# final_esp32_pc_heart_v2_3.net
KiCad netlist of a schematic drawn in EAGLE
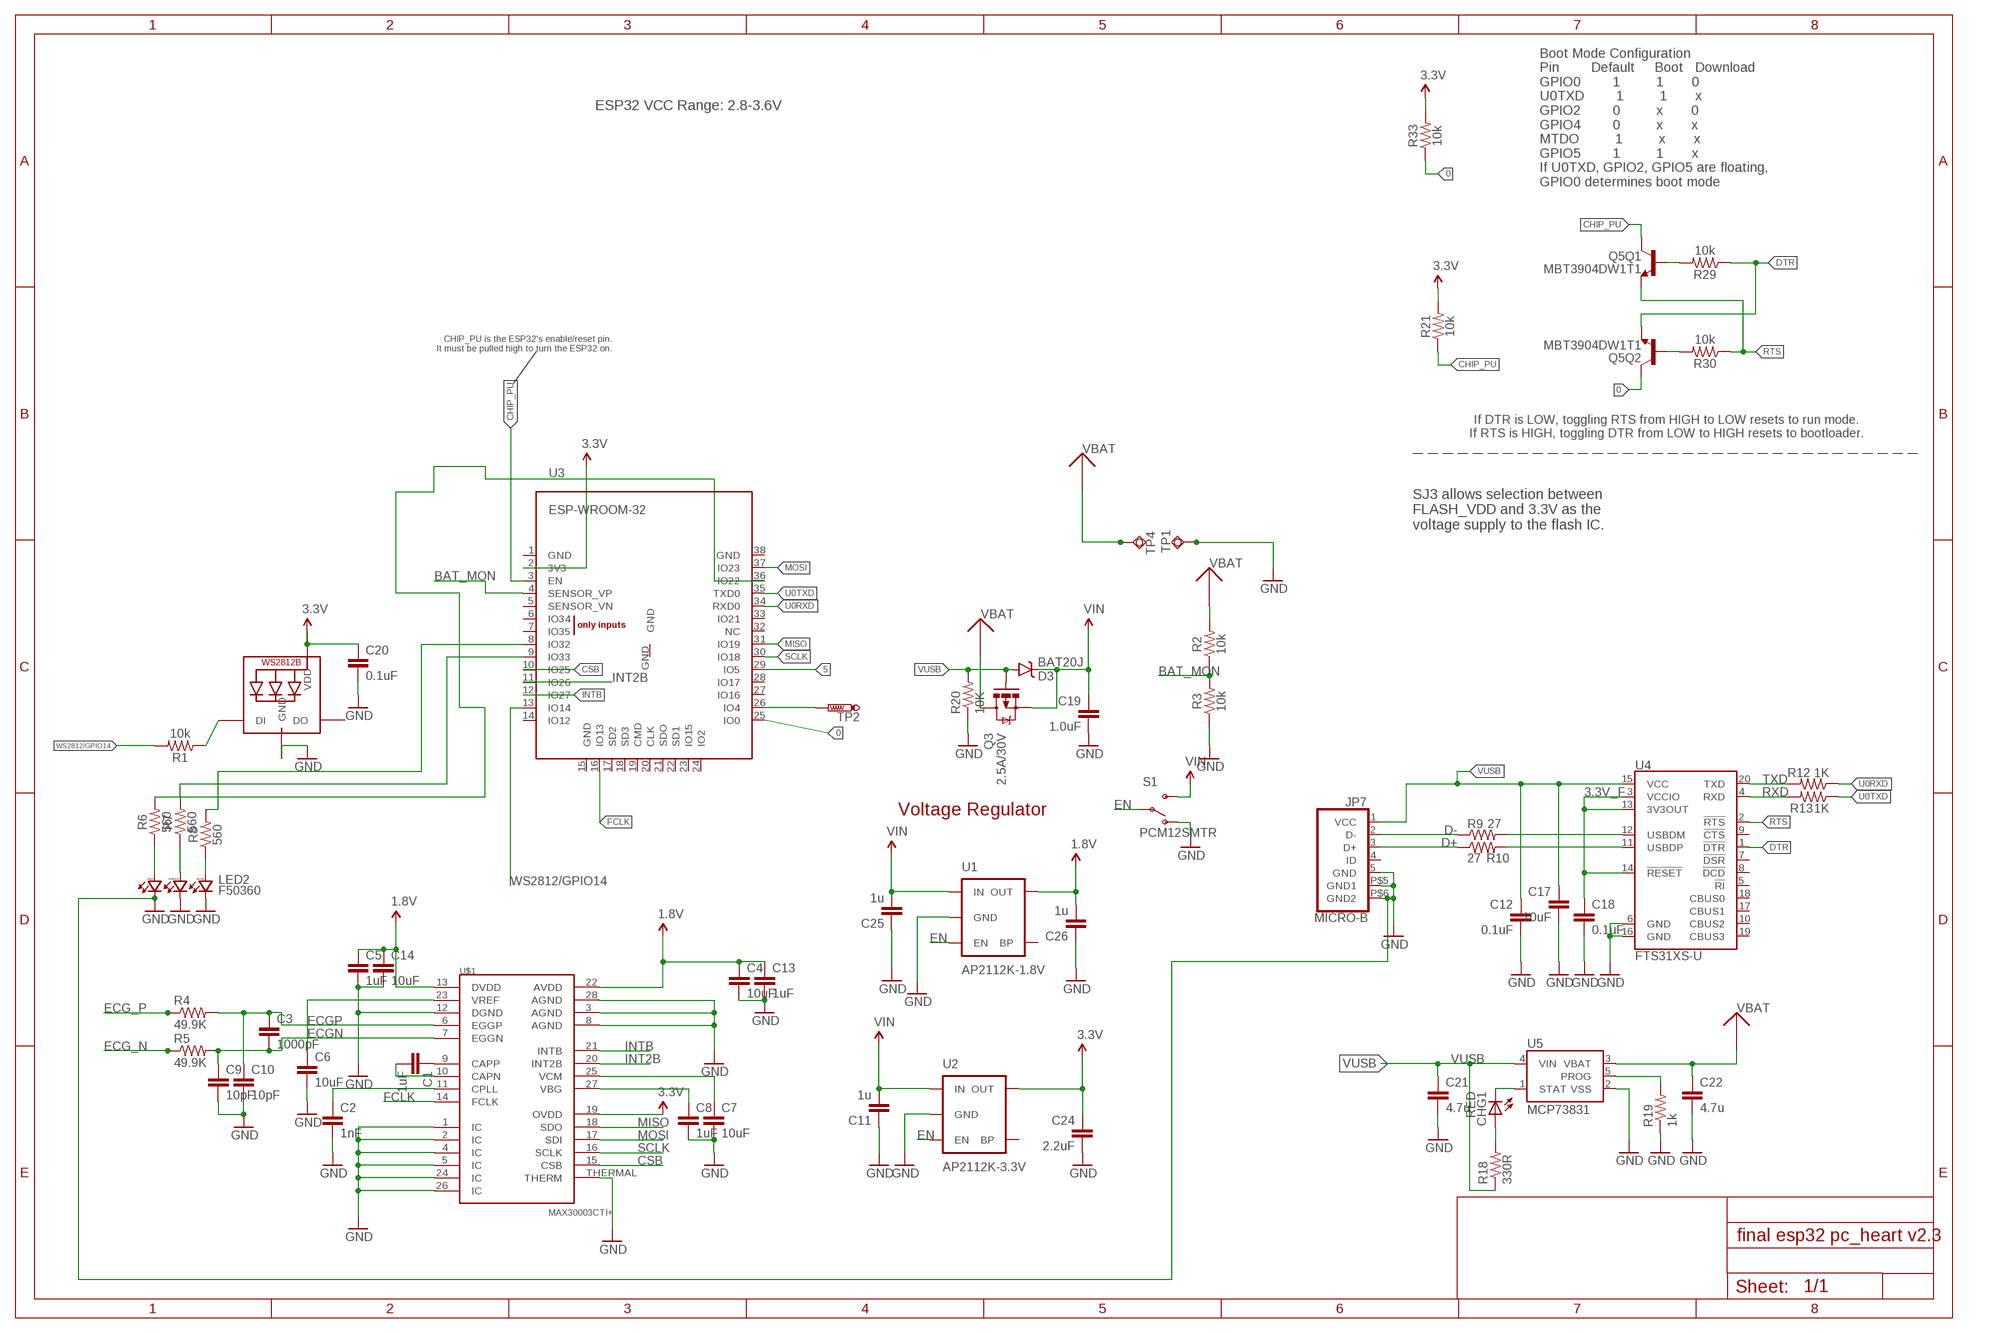
[diagram p0: schematic, sheet 1]

(export (version "E")
  (design (tool "Eeschema 10.0.6"))
  (components
    (comp (ref "C1")
      (value "1uF")
      (footprint "eagle-import:C0603")
      (libsource (lib "eagle-import") (part "C-EUC0603"))
    )
    (comp (ref "C2")
      (value "1nF")
      (footprint "eagle-import:C0603")
      (libsource (lib "eagle-import") (part "C-EUC0603"))
    )
    (comp (ref "C3")
      (value "1000pF")
      (footprint "eagle-import:C0402")
      (libsource (lib "eagle-import") (part "C-EUC0402"))
    )
    (comp (ref "C4")
      (value "10uF")
      (footprint "eagle-import:C0805")
      (libsource (lib "eagle-import") (part "C-EUC0805"))
    )
    (comp (ref "C5")
      (value "1uF")
      (footprint "eagle-import:C0402")
      (libsource (lib "eagle-import") (part "C-EUC0402"))
    )
    (comp (ref "C6")
      (value "10uF")
      (footprint "eagle-import:C0805")
      (libsource (lib "eagle-import") (part "C-EUC0805"))
    )
    (comp (ref "C7")
      (value "10uF")
      (footprint "eagle-import:C0805")
      (libsource (lib "eagle-import") (part "C-EUC0805"))
    )
    (comp (ref "C8")
      (value "1uF")
      (footprint "eagle-import:C0805")
      (libsource (lib "eagle-import") (part "C-EUC0805"))
    )
    (comp (ref "C9")
      (value "10pF")
      (footprint "eagle-import:C0402")
      (libsource (lib "eagle-import") (part "C-EUC0402"))
    )
    (comp (ref "C10")
      (value "10pF")
      (footprint "eagle-import:C0402")
      (libsource (lib "eagle-import") (part "C-EUC0402"))
    )
    (comp (ref "C11")
      (value "1u")
      (footprint "eagle-import:C0402")
      (libsource (lib "eagle-import") (part "C-EUC0402"))
    )
    (comp (ref "C12")
      (value "0.1uF")
      (footprint "eagle-import:C0402")
      (libsource (lib "eagle-import") (part "C-EUC0402"))
    )
    (comp (ref "C13")
      (value "1uF")
      (footprint "eagle-import:C0805")
      (libsource (lib "eagle-import") (part "C-EUC0805"))
    )
    (comp (ref "C14")
      (value "10uF")
      (footprint "eagle-import:C0603")
      (libsource (lib "eagle-import") (part "C-EUC0603"))
    )
    (comp (ref "C17")
      (value "10uF")
      (footprint "eagle-import:C0805")
      (libsource (lib "eagle-import") (part "C-EUC0805"))
    )
    (comp (ref "C18")
      (value "0.1uF")
      (footprint "eagle-import:C0402")
      (libsource (lib "eagle-import") (part "C-EUC0402"))
    )
    (comp (ref "C19")
      (value "1.0uF")
      (footprint "eagle-import:C0402")
      (libsource (lib "eagle-import") (part "C-EUC0402"))
    )
    (comp (ref "C20")
      (value "0.1uF")
      (footprint "eagle-import:0603")
      (libsource (lib "eagle-import") (part "0.1UF-0603-25V-(+80/-20%)"))
    )
    (comp (ref "C21")
      (value "4.7u")
      (footprint "eagle-import:C0805")
      (libsource (lib "eagle-import") (part "C-EUC0805"))
    )
    (comp (ref "C22")
      (value "4.7u")
      (footprint "eagle-import:C0805")
      (libsource (lib "eagle-import") (part "C-EUC0805"))
    )
    (comp (ref "C24")
      (value "2.2uF")
      (footprint "eagle-import:C0603")
      (libsource (lib "eagle-import") (part "C-EUC0603"))
    )
    (comp (ref "C25")
      (value "1u")
      (footprint "eagle-import:C0402")
      (libsource (lib "eagle-import") (part "C-EUC0402"))
    )
    (comp (ref "C26")
      (value "1u")
      (footprint "eagle-import:C0402")
      (libsource (lib "eagle-import") (part "C-EUC0402"))
    )
    (comp (ref "CHG1")
      (value "RED")
      (footprint "eagle-import:CHIPLED_0603")
      (libsource (lib "eagle-import") (part "LEDCHIPLED_0603"))
    )
    (comp (ref "D3")
      (value "BAT20J")
      (footprint "eagle-import:SOD-323")
      (libsource (lib "eagle-import") (part "DIODE-SCHOTTKY-BAT20J"))
    )
    (comp (ref "JP7")
      (value "MICRO-B")
      (footprint "eagle-import:MICRO-B")
      (libsource (lib "eagle-import") (part "MICRO-B"))
    )
    (comp (ref "LED1")
      (value "WS2812B5050")
      (footprint "eagle-import:WS2812B")
      (libsource (lib "eagle-import") (part "WS2812B5050"))
    )
    (comp (ref "LED2")
      (value "F50360")
      (footprint "eagle-import:F50360")
      (libsource (lib "eagle-import") (part "F50360"))
    )
    (comp (ref "Q3")
      (value "2.5A/30V")
      (footprint "eagle-import:SOT23-3")
      (libsource (lib "eagle-import") (part "MOSFET-PCHANNELDMG2307L"))
    )
    (comp (ref "Q5")
      (value "MBT3904DW1T1")
      (footprint "eagle-import:SC70-6")
      (libsource (lib "eagle-import") (part "MBT3904DW1T1"))
    )
    (comp (ref "R1")
      (value "10k")
      (footprint "eagle-import:0603")
      (libsource (lib "eagle-import") (part "10KOHM-1/10W-1%(0603)0603"))
    )
    (comp (ref "R2")
      (value "10k")
      (footprint "eagle-import:0603")
      (libsource (lib "eagle-import") (part "10KOHM-1/10W-1%(0603)0603"))
    )
    (comp (ref "R3")
      (value "10k")
      (footprint "eagle-import:0603")
      (libsource (lib "eagle-import") (part "10KOHM-1/10W-1%(0603)0603"))
    )
    (comp (ref "R4")
      (value "49.9K")
      (footprint "eagle-import:0805")
      (libsource (lib "eagle-import") (part "RESISTOR0805-RES"))
    )
    (comp (ref "R5")
      (value "49.9K")
      (footprint "eagle-import:0805")
      (libsource (lib "eagle-import") (part "RESISTOR0805-RES"))
    )
    (comp (ref "R6")
      (value "560")
      (footprint "eagle-import:0603")
      (libsource (lib "eagle-import") (part "10KOHM-1/10W-1%(0603)0603"))
    )
    (comp (ref "R7")
      (value "560")
      (footprint "eagle-import:0603")
      (libsource (lib "eagle-import") (part "10KOHM-1/10W-1%(0603)0603"))
    )
    (comp (ref "R8")
      (value "560")
      (footprint "eagle-import:0603")
      (libsource (lib "eagle-import") (part "10KOHM-1/10W-1%(0603)0603"))
    )
    (comp (ref "R9")
      (value "27")
      (footprint "eagle-import:R0402")
      (libsource (lib "eagle-import") (part "R-US_R0402"))
    )
    (comp (ref "R10")
      (value "27")
      (footprint "eagle-import:R0402")
      (libsource (lib "eagle-import") (part "R-US_R0402"))
    )
    (comp (ref "R12")
      (value "1K")
      (footprint "eagle-import:R0402")
      (libsource (lib "eagle-import") (part "R-US_R0402"))
    )
    (comp (ref "R13")
      (value "1K")
      (footprint "eagle-import:R0402")
      (libsource (lib "eagle-import") (part "R-US_R0402"))
    )
    (comp (ref "R18")
      (value "330R")
      (footprint "eagle-import:R0402")
      (libsource (lib "eagle-import") (part "R-US_R0402"))
    )
    (comp (ref "R19")
      (value "1k")
      (footprint "eagle-import:R0402")
      (libsource (lib "eagle-import") (part "R-US_R0402"))
    )
    (comp (ref "R20")
      (value "10K")
      (footprint "eagle-import:R0402")
      (libsource (lib "eagle-import") (part "R-US_R0402"))
    )
    (comp (ref "R21")
      (value "10k")
      (footprint "eagle-import:0603")
      (libsource (lib "eagle-import") (part "10KOHM-1/10W-1%(0603)0603"))
    )
    (comp (ref "R29")
      (value "10k")
      (footprint "eagle-import:0603")
      (libsource (lib "eagle-import") (part "10KOHM-0603-1/10W-1%"))
    )
    (comp (ref "R30")
      (value "10k")
      (footprint "eagle-import:0603")
      (libsource (lib "eagle-import") (part "10KOHM-0603-1/10W-1%"))
    )
    (comp (ref "R33")
      (value "10k")
      (footprint "eagle-import:0603")
      (libsource (lib "eagle-import") (part "10KOHM-1/10W-1%(0603)0603"))
    )
    (comp (ref "S1")
      (value "PCM12SMTR")
      (footprint "eagle-import:SWITCH-SPST-SMD-A")
      (libsource (lib "eagle-import") (part "SWITCH-SPDT-SMD-A"))
    )
    (comp (ref "TP1")
      (value "TPSQTP20SQ")
      (footprint "eagle-import:TP20SQ")
      (libsource (lib "eagle-import") (part "TPSQTP20SQ"))
    )
    (comp (ref "TP2")
      (value "PTR1TP10SQ")
      (footprint "eagle-import:TP10SQ")
      (libsource (lib "eagle-import") (part "PTR1TP10SQ"))
    )
    (comp (ref "TP4")
      (value "TPSQTP20SQ")
      (footprint "eagle-import:TP20SQ")
      (libsource (lib "eagle-import") (part "TPSQTP20SQ"))
    )
    (comp (ref "U$1")
      (value "MAX30003CTI+")
      (footprint "eagle-import:QFN-28")
      (libsource (lib "eagle-import") (part "MAX30003"))
    )
    (comp (ref "U1")
      (value "AP2112K-1.8V")
      (footprint "eagle-import:SOT23-5")
      (libsource (lib "eagle-import") (part "V_REG_LDOSMD"))
    )
    (comp (ref "U2")
      (value "AP2112K-3.3V")
      (footprint "eagle-import:SOT23-5")
      (libsource (lib "eagle-import") (part "V_REG_LDOSMD"))
    )
    (comp (ref "U3")
      (value "ESP-WROOM-32")
      (footprint "eagle-import:ESP-WROOM-32")
      (libsource (lib "eagle-import") (part "ESP-WROOM-32"))
    )
    (comp (ref "U4")
      (value "FTS31XS-U")
      (footprint "eagle-import:SSOP20_L")
      (libsource (lib "eagle-import") (part "FT231XS"))
    )
    (comp (ref "U5")
      (value "MCP73831")
      (footprint "eagle-import:SOT23-5")
      (libsource (lib "eagle-import") (part "MCP73831"))
    )
  )
  (nets
    (net (code "1") (name "/3.3V_F") (class "Default")
      (node (ref "C18") (pin "1") (pinfunction "1_1") (pintype "passive"))
      (node (ref "U4") (pin "13") (pinfunction "3V3OUT_13") (pintype "bidirectional"))
      (node (ref "U4") (pin "14") (pinfunction "~{RESET}_14") (pintype "bidirectional"))
      (node (ref "U4") (pin "3") (pinfunction "VCCIO_3") (pintype "bidirectional"))
    )
    (net (code "2") (name "/BAT_MON") (class "Default")
      (node (ref "R2") (pin "1") (pinfunction "1_1") (pintype "passive"))
      (node (ref "R3") (pin "2") (pinfunction "2_2") (pintype "passive"))
      (node (ref "U3") (pin "4") (pinfunction "SENSOR_VP_4") (pintype "input"))
    )
    (net (code "3") (name "/D+") (class "Default")
      (node (ref "JP7") (pin "3") (pinfunction "D+_3") (pintype "bidirectional"))
      (node (ref "R10") (pin "1") (pinfunction "1_1") (pintype "passive"))
    )
    (net (code "4") (name "/D-") (class "Default")
      (node (ref "JP7") (pin "2") (pinfunction "D-_2") (pintype "bidirectional"))
      (node (ref "R9") (pin "1") (pinfunction "1_1") (pintype "passive"))
    )
    (net (code "5") (name "/ECGN") (class "Default")
      (node (ref "C3") (pin "2") (pinfunction "2_2") (pintype "passive"))
      (node (ref "C9") (pin "1") (pinfunction "1_1") (pintype "passive"))
      (node (ref "R5") (pin "2") (pinfunction "2_2") (pintype "passive"))
      (node (ref "U$1") (pin "7") (pinfunction "EGGN_7") (pintype "bidirectional"))
    )
    (net (code "6") (name "/ECGP") (class "Default")
      (node (ref "C10") (pin "1") (pinfunction "1_1") (pintype "passive"))
      (node (ref "C3") (pin "1") (pinfunction "1_1") (pintype "passive"))
      (node (ref "R4") (pin "2") (pinfunction "2_2") (pintype "passive"))
      (node (ref "U$1") (pin "6") (pinfunction "EGGP_6") (pintype "bidirectional"))
    )
    (net (code "7") (name "/ECG_N") (class "Default")
      (node (ref "R5") (pin "1") (pinfunction "1_1") (pintype "passive"))
    )
    (net (code "8") (name "/ECG_P") (class "Default")
      (node (ref "R4") (pin "1") (pinfunction "1_1") (pintype "passive"))
    )
    (net (code "9") (name "/EN") (class "Default")
      (node (ref "S1") (pin "2") (pinfunction "P_2") (pintype "passive"))
      (node (ref "U1") (pin "3") (pinfunction "EN_3") (pintype "input"))
      (node (ref "U2") (pin "3") (pinfunction "EN_3") (pintype "input"))
    )
    (net (code "10") (name "/INT2B") (class "Default")
      (node (ref "U$1") (pin "20") (pinfunction "INT2B_20") (pintype "bidirectional"))
      (node (ref "U3") (pin "11") (pinfunction "IO26_11") (pintype "bidirectional"))
    )
    (net (code "11") (name "/RXD") (class "Default")
      (node (ref "R13") (pin "2") (pinfunction "2_2") (pintype "passive"))
      (node (ref "U4") (pin "4") (pinfunction "RXD_4") (pintype "bidirectional"))
    )
    (net (code "12") (name "/TXD") (class "Default")
      (node (ref "R12") (pin "2") (pinfunction "2_2") (pintype "passive"))
      (node (ref "U4") (pin "20") (pinfunction "TXD_20") (pintype "bidirectional"))
    )
    (net (code "13") (name "0") (class "Default")
      (node (ref "Q5") (pin "6") (pinfunction "C_6") (pintype "passive"))
      (node (ref "R33") (pin "1") (pinfunction "1_1") (pintype "passive"))
      (node (ref "U3") (pin "25") (pinfunction "IO0_25") (pintype "bidirectional"))
    )
    (net (code "14") (name "1.8V") (class "Default")
      (node (ref "C13") (pin "1") (pinfunction "1_1") (pintype "passive"))
      (node (ref "C14") (pin "1") (pinfunction "1_1") (pintype "passive"))
      (node (ref "C26") (pin "2") (pinfunction "2_2") (pintype "passive"))
      (node (ref "C4") (pin "1") (pinfunction "1_1") (pintype "passive"))
      (node (ref "C5") (pin "1") (pinfunction "1_1") (pintype "passive"))
      (node (ref "U$1") (pin "13") (pinfunction "DVDD_13") (pintype "bidirectional"))
      (node (ref "U$1") (pin "22") (pinfunction "AVDD_22") (pintype "bidirectional"))
      (node (ref "U1") (pin "5") (pinfunction "OUT_5") (pintype "passive"))
    )
    (net (code "15") (name "3.3V") (class "Default")
      (node (ref "C20") (pin "1") (pinfunction "1_1") (pintype "passive"))
      (node (ref "C24") (pin "1") (pinfunction "1_1") (pintype "passive"))
      (node (ref "LED1") (pin "1-VDD") (pinfunction "VDD_1-VDD") (pintype "power_in"))
      (node (ref "R21") (pin "2") (pinfunction "2_2") (pintype "passive"))
      (node (ref "R33") (pin "2") (pinfunction "2_2") (pintype "passive"))
      (node (ref "U$1") (pin "19") (pinfunction "OVDD_19") (pintype "bidirectional"))
      (node (ref "U2") (pin "5") (pinfunction "OUT_5") (pintype "passive"))
      (node (ref "U3") (pin "2") (pinfunction "3V3_2") (pintype "bidirectional"))
    )
    (net (code "16") (name "5") (class "Default")
      (node (ref "U3") (pin "29") (pinfunction "IO5_29") (pintype "bidirectional"))
    )
    (net (code "17") (name "CHIP_PU") (class "Default")
      (node (ref "Q5") (pin "3") (pinfunction "C_3") (pintype "passive"))
      (node (ref "R21") (pin "1") (pinfunction "1_1") (pintype "passive"))
      (node (ref "U3") (pin "3") (pinfunction "EN_3") (pintype "bidirectional"))
    )
    (net (code "18") (name "CSB") (class "Default")
      (node (ref "U$1") (pin "15") (pinfunction "CSB_15") (pintype "bidirectional"))
      (node (ref "U3") (pin "10") (pinfunction "IO25_10") (pintype "bidirectional"))
    )
    (net (code "19") (name "DTR") (class "Default")
      (node (ref "Q5") (pin "1") (pinfunction "E_1") (pintype "passive"))
      (node (ref "R29") (pin "1") (pinfunction "1_1") (pintype "passive"))
      (node (ref "U4") (pin "1") (pinfunction "~{DTR}_1") (pintype "bidirectional"))
    )
    (net (code "20") (name "FCLK") (class "Default")
      (node (ref "U$1") (pin "14") (pinfunction "FCLK_14") (pintype "bidirectional"))
      (node (ref "U3") (pin "16") (pinfunction "IO13_16") (pintype "bidirectional"))
    )
    (net (code "21") (name "GND") (class "Default")
      (node (ref "C10") (pin "2") (pinfunction "2_2") (pintype "passive"))
      (node (ref "C11") (pin "1") (pinfunction "1_1") (pintype "passive"))
      (node (ref "C12") (pin "2") (pinfunction "2_2") (pintype "passive"))
      (node (ref "C13") (pin "2") (pinfunction "2_2") (pintype "passive"))
      (node (ref "C14") (pin "2") (pinfunction "2_2") (pintype "passive"))
      (node (ref "C17") (pin "2") (pinfunction "2_2") (pintype "passive"))
      (node (ref "C18") (pin "2") (pinfunction "2_2") (pintype "passive"))
      (node (ref "C19") (pin "2") (pinfunction "2_2") (pintype "passive"))
      (node (ref "C2") (pin "2") (pinfunction "2_2") (pintype "passive"))
      (node (ref "C20") (pin "2") (pinfunction "2_2") (pintype "passive"))
      (node (ref "C21") (pin "2") (pinfunction "2_2") (pintype "passive"))
      (node (ref "C22") (pin "2") (pinfunction "2_2") (pintype "passive"))
      (node (ref "C24") (pin "2") (pinfunction "2_2") (pintype "passive"))
      (node (ref "C25") (pin "1") (pinfunction "1_1") (pintype "passive"))
      (node (ref "C26") (pin "1") (pinfunction "1_1") (pintype "passive"))
      (node (ref "C4") (pin "2") (pinfunction "2_2") (pintype "passive"))
      (node (ref "C5") (pin "2") (pinfunction "2_2") (pintype "passive"))
      (node (ref "C6") (pin "2") (pinfunction "2_2") (pintype "passive"))
      (node (ref "C7") (pin "2") (pinfunction "2_2") (pintype "passive"))
      (node (ref "C8") (pin "2") (pinfunction "2_2") (pintype "passive"))
      (node (ref "C9") (pin "2") (pinfunction "2_2") (pintype "passive"))
      (node (ref "JP7") (pin "5") (pinfunction "GND_5") (pintype "bidirectional"))
      (node (ref "JP7") (pin "P$5") (pinfunction "GND1_P$5") (pintype "bidirectional"))
      (node (ref "JP7") (pin "P$6") (pinfunction "GND2_P$6") (pintype "bidirectional"))
      (node (ref "LED1") (pin "3-GND") (pinfunction "GND_3-GND") (pintype "power_in"))
      (node (ref "LED2") (pin "BC") (pinfunction "BC_BC") (pintype "passive"))
      (node (ref "LED2") (pin "GC") (pinfunction "GC_GC") (pintype "passive"))
      (node (ref "LED2") (pin "RC") (pinfunction "RC_RC") (pintype "passive"))
      (node (ref "R19") (pin "1") (pinfunction "1_1") (pintype "passive"))
      (node (ref "R20") (pin "1") (pinfunction "1_1") (pintype "passive"))
      (node (ref "R3") (pin "1") (pinfunction "1_1") (pintype "passive"))
      (node (ref "S1") (pin "1") (pinfunction "O_1") (pintype "passive"))
      (node (ref "TP1") (pin "TP") (pinfunction "TP_TP") (pintype "input"))
      (node (ref "U$1") (pin "1") (pinfunction "IC_1") (pintype "bidirectional"))
      (node (ref "U$1") (pin "12") (pinfunction "DGND_12") (pintype "bidirectional"))
      (node (ref "U$1") (pin "2") (pinfunction "IC_2") (pintype "bidirectional"))
      (node (ref "U$1") (pin "24") (pinfunction "IC_24") (pintype "bidirectional"))
      (node (ref "U$1") (pin "26") (pinfunction "IC_26") (pintype "bidirectional"))
      (node (ref "U$1") (pin "28") (pinfunction "AGND_28") (pintype "bidirectional"))
      (node (ref "U$1") (pin "3") (pinfunction "AGND_3") (pintype "bidirectional"))
      (node (ref "U$1") (pin "4") (pinfunction "IC_4") (pintype "bidirectional"))
      (node (ref "U$1") (pin "5") (pinfunction "IC_5") (pintype "bidirectional"))
      (node (ref "U$1") (pin "8") (pinfunction "AGND_8") (pintype "bidirectional"))
      (node (ref "U$1") (pin "THERMAL") (pinfunction "THERM_THERMAL") (pintype "bidirectional"))
      (node (ref "U1") (pin "2") (pinfunction "GND_2") (pintype "input"))
      (node (ref "U2") (pin "2") (pinfunction "GND_2") (pintype "input"))
      (node (ref "U4") (pin "16") (pinfunction "GND_16") (pintype "bidirectional"))
      (node (ref "U4") (pin "6") (pinfunction "GND_6") (pintype "bidirectional"))
      (node (ref "U5") (pin "2") (pinfunction "VSS_2") (pintype "power_in"))
    )
    (net (code "22") (name "INTB") (class "Default")
      (node (ref "U$1") (pin "21") (pinfunction "INTB_21") (pintype "bidirectional"))
      (node (ref "U3") (pin "12") (pinfunction "IO27_12") (pintype "bidirectional"))
    )
    (net (code "23") (name "MISO") (class "Default")
      (node (ref "U$1") (pin "18") (pinfunction "SDO_18") (pintype "bidirectional"))
      (node (ref "U3") (pin "31") (pinfunction "IO19_31") (pintype "bidirectional"))
    )
    (net (code "24") (name "MOSI") (class "Default")
      (node (ref "U$1") (pin "17") (pinfunction "SDI_17") (pintype "bidirectional"))
      (node (ref "U3") (pin "37") (pinfunction "IO23_37") (pintype "bidirectional"))
    )
    (net (code "25") (name "Net-(CHG1-PadA)") (class "Default")
      (node (ref "CHG1") (pin "A") (pinfunction "A_A") (pintype "passive"))
      (node (ref "R18") (pin "2") (pinfunction "2_2") (pintype "passive"))
    )
    (net (code "26") (name "Net-(LED1-DI)") (class "Default")
      (node (ref "LED1") (pin "4-DIN") (pinfunction "DI_4-DIN") (pintype "input"))
      (node (ref "R1") (pin "1") (pinfunction "1_1") (pintype "passive"))
    )
    (net (code "27") (name "Net-(LED2-PadBA)") (class "Default")
      (node (ref "LED2") (pin "BA") (pinfunction "BA_BA") (pintype "passive"))
      (node (ref "R8") (pin "1") (pinfunction "1_1") (pintype "passive"))
    )
    (net (code "28") (name "Net-(LED2-PadGA)") (class "Default")
      (node (ref "LED2") (pin "GA") (pinfunction "GA_GA") (pintype "passive"))
      (node (ref "R7") (pin "1") (pinfunction "1_1") (pintype "passive"))
    )
    (net (code "29") (name "Net-(LED2-PadRA)") (class "Default")
      (node (ref "LED2") (pin "RA") (pinfunction "RA_RA") (pintype "passive"))
      (node (ref "R6") (pin "1") (pinfunction "1_1") (pintype "passive"))
    )
    (net (code "30") (name "Net-(Q5A-B)") (class "Default")
      (node (ref "Q5") (pin "5") (pinfunction "B_5") (pintype "passive"))
      (node (ref "R29") (pin "2") (pinfunction "2_2") (pintype "passive"))
    )
    (net (code "31") (name "Net-(Q5B-B)") (class "Default")
      (node (ref "Q5") (pin "2") (pinfunction "B_2") (pintype "passive"))
      (node (ref "R30") (pin "2") (pinfunction "2_2") (pintype "passive"))
    )
    (net (code "32") (name "Net-(U$1-CAPN)") (class "Default")
      (node (ref "C1") (pin "2") (pinfunction "2_2") (pintype "passive"))
      (node (ref "U$1") (pin "10") (pinfunction "CAPN_10") (pintype "bidirectional"))
    )
    (net (code "33") (name "Net-(U$1-CAPP)") (class "Default")
      (node (ref "C1") (pin "1") (pinfunction "1_1") (pintype "passive"))
      (node (ref "U$1") (pin "9") (pinfunction "CAPP_9") (pintype "bidirectional"))
    )
    (net (code "34") (name "Net-(U$1-CPLL)") (class "Default")
      (node (ref "C2") (pin "1") (pinfunction "1_1") (pintype "passive"))
      (node (ref "U$1") (pin "11") (pinfunction "CPLL_11") (pintype "bidirectional"))
    )
    (net (code "35") (name "Net-(U$1-VBG)") (class "Default")
      (node (ref "C8") (pin "1") (pinfunction "1_1") (pintype "passive"))
      (node (ref "U$1") (pin "27") (pinfunction "VBG_27") (pintype "bidirectional"))
    )
    (net (code "36") (name "Net-(U$1-VCM)") (class "Default")
      (node (ref "C7") (pin "1") (pinfunction "1_1") (pintype "passive"))
      (node (ref "U$1") (pin "25") (pinfunction "VCM_25") (pintype "bidirectional"))
    )
    (net (code "37") (name "Net-(U$1-VREF)") (class "Default")
      (node (ref "C6") (pin "1") (pinfunction "1_1") (pintype "passive"))
      (node (ref "U$1") (pin "23") (pinfunction "VREF_23") (pintype "bidirectional"))
    )
    (net (code "38") (name "Net-(U3-IO4)") (class "Default")
      (node (ref "TP2") (pin "TP") (pinfunction "TP_TP") (pintype "input"))
      (node (ref "U3") (pin "26") (pinfunction "IO4_26") (pintype "bidirectional"))
    )
    (net (code "39") (name "Net-(U3-IO22)") (class "Default")
      (node (ref "R6") (pin "2") (pinfunction "2_2") (pintype "passive"))
      (node (ref "U3") (pin "36") (pinfunction "IO22_36") (pintype "bidirectional"))
    )
    (net (code "40") (name "Net-(U3-IO32)") (class "Default")
      (node (ref "R8") (pin "2") (pinfunction "2_2") (pintype "passive"))
      (node (ref "U3") (pin "8") (pinfunction "IO32_8") (pintype "bidirectional"))
    )
    (net (code "41") (name "Net-(U3-IO33)") (class "Default")
      (node (ref "R7") (pin "2") (pinfunction "2_2") (pintype "passive"))
      (node (ref "U3") (pin "9") (pinfunction "IO33_9") (pintype "bidirectional"))
    )
    (net (code "42") (name "Net-(U4-USBDM)") (class "Default")
      (node (ref "R9") (pin "2") (pinfunction "2_2") (pintype "passive"))
      (node (ref "U4") (pin "12") (pinfunction "USBDM_12") (pintype "bidirectional"))
    )
    (net (code "43") (name "Net-(U4-USBDP)") (class "Default")
      (node (ref "R10") (pin "2") (pinfunction "2_2") (pintype "passive"))
      (node (ref "U4") (pin "11") (pinfunction "USBDP_11") (pintype "bidirectional"))
    )
    (net (code "44") (name "Net-(U5-PROG)") (class "Default")
      (node (ref "R19") (pin "2") (pinfunction "2_2") (pintype "passive"))
      (node (ref "U5") (pin "5") (pinfunction "PROG_5") (pintype "input"))
    )
    (net (code "45") (name "Net-(U5-STAT)") (class "Default")
      (node (ref "CHG1") (pin "C") (pinfunction "C_C") (pintype "passive"))
      (node (ref "U5") (pin "1") (pinfunction "STAT_1") (pintype "output"))
    )
    (net (code "46") (name "RTS") (class "Default")
      (node (ref "Q5") (pin "4") (pinfunction "E_4") (pintype "passive"))
      (node (ref "R30") (pin "1") (pinfunction "1_1") (pintype "passive"))
      (node (ref "U4") (pin "2") (pinfunction "~{RTS}_2") (pintype "bidirectional"))
    )
    (net (code "47") (name "SCLK") (class "Default")
      (node (ref "U$1") (pin "16") (pinfunction "SCLK_16") (pintype "bidirectional"))
      (node (ref "U3") (pin "30") (pinfunction "IO18_30") (pintype "bidirectional"))
    )
    (net (code "48") (name "U0RXD") (class "Default")
      (node (ref "R12") (pin "1") (pinfunction "1_1") (pintype "passive"))
      (node (ref "U3") (pin "34") (pinfunction "RXD0_34") (pintype "bidirectional"))
    )
    (net (code "49") (name "U0TXD") (class "Default")
      (node (ref "R13") (pin "1") (pinfunction "1_1") (pintype "passive"))
      (node (ref "U3") (pin "35") (pinfunction "TXD0_35") (pintype "bidirectional"))
    )
    (net (code "50") (name "VBAT") (class "Default")
      (node (ref "C22") (pin "1") (pinfunction "1_1") (pintype "passive"))
      (node (ref "Q3") (pin "3") (pinfunction "D_3") (pintype "passive"))
      (node (ref "R2") (pin "2") (pinfunction "2_2") (pintype "passive"))
      (node (ref "TP4") (pin "TP") (pinfunction "TP_TP") (pintype "input"))
      (node (ref "U5") (pin "3") (pinfunction "VBAT_3") (pintype "power_in"))
    )
    (net (code "51") (name "VIN") (class "Default")
      (node (ref "C11") (pin "2") (pinfunction "2_2") (pintype "passive"))
      (node (ref "C19") (pin "1") (pinfunction "1_1") (pintype "passive"))
      (node (ref "C25") (pin "2") (pinfunction "2_2") (pintype "passive"))
      (node (ref "D3") (pin "C") (pinfunction "C_C") (pintype "passive"))
      (node (ref "Q3") (pin "2") (pinfunction "S_2") (pintype "passive"))
      (node (ref "S1") (pin "3") (pinfunction "S_3") (pintype "passive"))
      (node (ref "U1") (pin "1") (pinfunction "IN_1") (pintype "input"))
      (node (ref "U2") (pin "1") (pinfunction "IN_1") (pintype "input"))
    )
    (net (code "52") (name "VUSB") (class "Default")
      (node (ref "C12") (pin "1") (pinfunction "1_1") (pintype "passive"))
      (node (ref "C17") (pin "1") (pinfunction "1_1") (pintype "passive"))
      (node (ref "C21") (pin "1") (pinfunction "1_1") (pintype "passive"))
      (node (ref "D3") (pin "A") (pinfunction "A_A") (pintype "passive"))
      (node (ref "JP7") (pin "1") (pinfunction "VCC_1") (pintype "bidirectional"))
      (node (ref "Q3") (pin "1") (pinfunction "G_1") (pintype "passive"))
      (node (ref "R18") (pin "1") (pinfunction "1_1") (pintype "passive"))
      (node (ref "R20") (pin "2") (pinfunction "2_2") (pintype "passive"))
      (node (ref "U4") (pin "15") (pinfunction "VCC_15") (pintype "bidirectional"))
      (node (ref "U5") (pin "4") (pinfunction "VIN_4") (pintype "power_in"))
    )
    (net (code "53") (name "WS2812{slash}GPIO14") (class "Default")
      (node (ref "R1") (pin "2") (pinfunction "2_2") (pintype "passive"))
      (node (ref "U3") (pin "13") (pinfunction "IO14_13") (pintype "bidirectional"))
    )
    (net (code "54") (name "unconnected-(JP7-ID-Pad4)") (class "Default")
      (node (ref "JP7") (pin "4") (pinfunction "ID_4") (pintype "bidirectional"))
    )
    (net (code "55") (name "unconnected-(LED1-DO-Pad2-DOUT)") (class "Default")
      (node (ref "LED1") (pin "2-DOUT") (pinfunction "DO_2-DOUT") (pintype "output"))
    )
    (net (code "56") (name "unconnected-(U1-BP-Pad4)") (class "Default")
      (node (ref "U1") (pin "4") (pinfunction "BP_4") (pintype "input"))
    )
    (net (code "57") (name "unconnected-(U2-BP-Pad4)") (class "Default")
      (node (ref "U2") (pin "4") (pinfunction "BP_4") (pintype "input"))
    )
    (net (code "58") (name "unconnected-(U3-CLK-Pad20)") (class "Default")
      (node (ref "U3") (pin "20") (pinfunction "CLK_20") (pintype "bidirectional"))
    )
    (net (code "59") (name "unconnected-(U3-CMD-Pad19)") (class "Default")
      (node (ref "U3") (pin "19") (pinfunction "CMD_19") (pintype "bidirectional"))
    )
    (net (code "60") (name "unconnected-(U3-GND-Pad1)") (class "Default")
      (node (ref "U3") (pin "1") (pinfunction "GND_1") (pintype "bidirectional"))
    )
    (net (code "61") (name "unconnected-(U3-GND-Pad15)") (class "Default")
      (node (ref "U3") (pin "15") (pinfunction "GND_15") (pintype "bidirectional"))
    )
    (net (code "62") (name "unconnected-(U3-GND-Pad38)") (class "Default")
      (node (ref "U3") (pin "38") (pinfunction "GND_38") (pintype "bidirectional"))
    )
    (net (code "63") (name "unconnected-(U3-IO2-Pad24)") (class "Default")
      (node (ref "U3") (pin "24") (pinfunction "IO2_24") (pintype "bidirectional"))
    )
    (net (code "64") (name "unconnected-(U3-IO12-Pad14)") (class "Default")
      (node (ref "U3") (pin "14") (pinfunction "IO12_14") (pintype "bidirectional"))
    )
    (net (code "65") (name "unconnected-(U3-IO15-Pad23)") (class "Default")
      (node (ref "U3") (pin "23") (pinfunction "IO15_23") (pintype "bidirectional"))
    )
    (net (code "66") (name "unconnected-(U3-IO16-Pad27)") (class "Default")
      (node (ref "U3") (pin "27") (pinfunction "IO16_27") (pintype "bidirectional"))
    )
    (net (code "67") (name "unconnected-(U3-IO17-Pad28)") (class "Default")
      (node (ref "U3") (pin "28") (pinfunction "IO17_28") (pintype "bidirectional"))
    )
    (net (code "68") (name "unconnected-(U3-IO21-Pad33)") (class "Default")
      (node (ref "U3") (pin "33") (pinfunction "IO21_33") (pintype "bidirectional"))
    )
    (net (code "69") (name "unconnected-(U3-IO34-Pad6)") (class "Default")
      (node (ref "U3") (pin "6") (pinfunction "IO34_6") (pintype "input"))
    )
    (net (code "70") (name "unconnected-(U3-IO35-Pad7)") (class "Default")
      (node (ref "U3") (pin "7") (pinfunction "IO35_7") (pintype "input"))
    )
    (net (code "71") (name "unconnected-(U3-NC-Pad32)") (class "Default")
      (node (ref "U3") (pin "32") (pinfunction "NC_32") (pintype "bidirectional"))
    )
    (net (code "72") (name "unconnected-(U3-PadGND)") (class "Default")
      (node (ref "U3") (pin "GND") (pinfunction "GND_GND") (pintype "bidirectional"))
    )
    (net (code "73") (name "unconnected-(U3-SD1-Pad22)") (class "Default")
      (node (ref "U3") (pin "22") (pinfunction "SD1_22") (pintype "bidirectional"))
    )
    (net (code "74") (name "unconnected-(U3-SD2-Pad17)") (class "Default")
      (node (ref "U3") (pin "17") (pinfunction "SD2_17") (pintype "bidirectional"))
    )
    (net (code "75") (name "unconnected-(U3-SD3-Pad18)") (class "Default")
      (node (ref "U3") (pin "18") (pinfunction "SD3_18") (pintype "bidirectional"))
    )
    (net (code "76") (name "unconnected-(U3-SDO-Pad21)") (class "Default")
      (node (ref "U3") (pin "21") (pinfunction "SDO_21") (pintype "bidirectional"))
    )
    (net (code "77") (name "unconnected-(U3-SENSOR_VN-Pad5)") (class "Default")
      (node (ref "U3") (pin "5") (pinfunction "SENSOR_VN_5") (pintype "input"))
    )
    (net (code "78") (name "unconnected-(U4-CBUS0-Pad18)") (class "Default")
      (node (ref "U4") (pin "18") (pinfunction "CBUS0_18") (pintype "bidirectional"))
    )
    (net (code "79") (name "unconnected-(U4-CBUS1-Pad17)") (class "Default")
      (node (ref "U4") (pin "17") (pinfunction "CBUS1_17") (pintype "bidirectional"))
    )
    (net (code "80") (name "unconnected-(U4-CBUS2-Pad10)") (class "Default")
      (node (ref "U4") (pin "10") (pinfunction "CBUS2_10") (pintype "bidirectional"))
    )
    (net (code "81") (name "unconnected-(U4-CBUS3-Pad19)") (class "Default")
      (node (ref "U4") (pin "19") (pinfunction "CBUS3_19") (pintype "bidirectional"))
    )
    (net (code "82") (name "unconnected-(U4-~{CTS}-Pad9)") (class "Default")
      (node (ref "U4") (pin "9") (pinfunction "~{CTS}_9") (pintype "bidirectional"))
    )
    (net (code "83") (name "unconnected-(U4-~{DCD}-Pad8)") (class "Default")
      (node (ref "U4") (pin "8") (pinfunction "~{DCD}_8") (pintype "bidirectional"))
    )
    (net (code "84") (name "unconnected-(U4-~{DSR}-Pad7)") (class "Default")
      (node (ref "U4") (pin "7") (pinfunction "~{DSR}_7") (pintype "bidirectional"))
    )
    (net (code "85") (name "unconnected-(U4-~{RI}-Pad5)") (class "Default")
      (node (ref "U4") (pin "5") (pinfunction "~{RI}_5") (pintype "bidirectional"))
    )
  )
)
